# MiataPopUpEnhancer.net
KiCad netlist of a schematic drawn in EAGLE
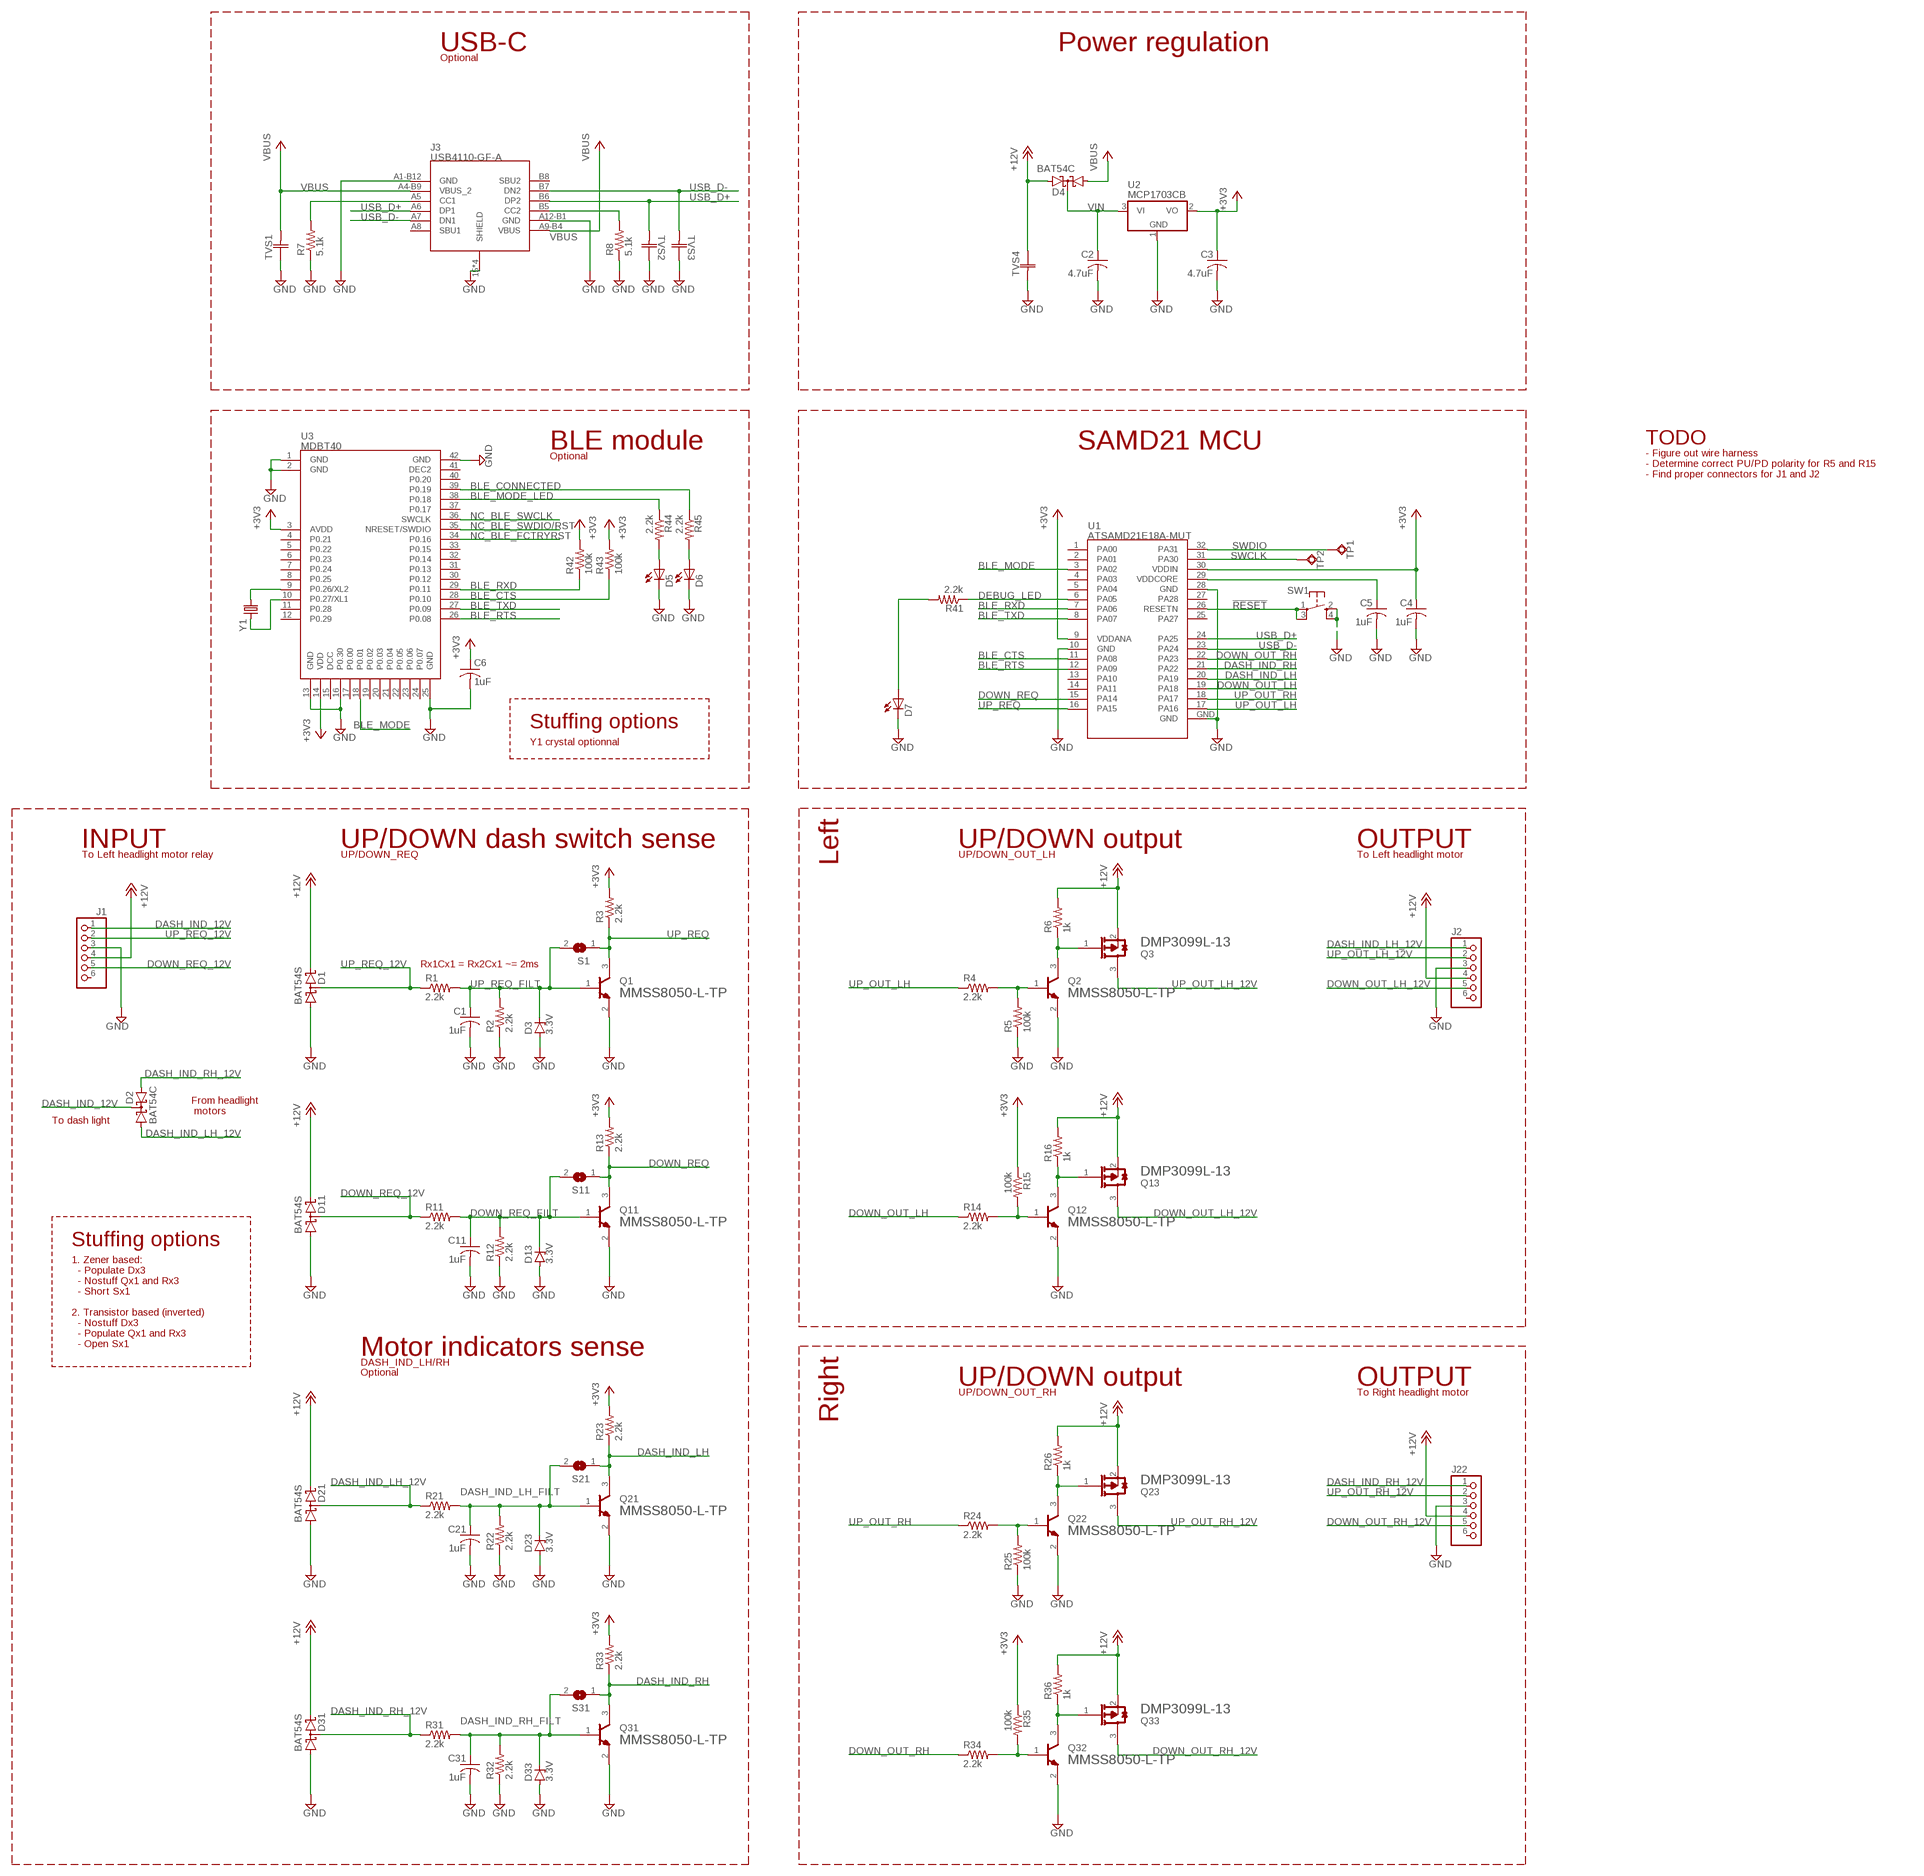
[diagram p0: schematic, sheet 1]

(export (version "E")
  (design (tool "Eeschema 10.0.6"))
  (components
    (comp (ref "C1")
      (value "1uF")
      (footprint "eagle-import:C0603")
      (libsource (lib "eagle-import") (part "C-USC0603"))
    )
    (comp (ref "C2")
      (value "4.7uF")
      (footprint "eagle-import:C0603K")
      (libsource (lib "eagle-import") (part "C-USC0603K"))
    )
    (comp (ref "C3")
      (value "4.7uF")
      (footprint "eagle-import:C0603")
      (libsource (lib "eagle-import") (part "C-USC0603"))
    )
    (comp (ref "C4")
      (value "1uF")
      (footprint "eagle-import:C0603")
      (libsource (lib "eagle-import") (part "C-USC0603"))
    )
    (comp (ref "C5")
      (value "1uF")
      (footprint "eagle-import:C0603")
      (libsource (lib "eagle-import") (part "C-USC0603"))
    )
    (comp (ref "C6")
      (value "1uF")
      (footprint "eagle-import:C0603")
      (libsource (lib "eagle-import") (part "C-USC0603"))
    )
    (comp (ref "C11")
      (value "1uF")
      (footprint "eagle-import:C0603")
      (libsource (lib "eagle-import") (part "C-USC0603"))
    )
    (comp (ref "C21")
      (value "1uF")
      (footprint "eagle-import:C0603")
      (libsource (lib "eagle-import") (part "C-USC0603"))
    )
    (comp (ref "C31")
      (value "1uF")
      (footprint "eagle-import:C0603")
      (libsource (lib "eagle-import") (part "C-USC0603"))
    )
    (comp (ref "D1")
      (value "BAT54S")
      (footprint "eagle-import:SOT23")
      (libsource (lib "eagle-import") (part "BAT54S"))
    )
    (comp (ref "D2")
      (value "BAT54C")
      (footprint "eagle-import:SOT23")
      (libsource (lib "eagle-import") (part "BAT54C"))
    )
    (comp (ref "D3")
      (value "3.3V")
      (footprint "eagle-import:TO236")
      (libsource (lib "eagle-import") (part "BZX84CSMD"))
    )
    (comp (ref "D4")
      (value "BAT54C")
      (footprint "eagle-import:SOT23")
      (libsource (lib "eagle-import") (part "BAT54C"))
    )
    (comp (ref "D5")
      (value "LEDCHIPLED_0603")
      (footprint "eagle-import:CHIPLED_0603")
      (libsource (lib "eagle-import") (part "LEDCHIPLED_0603"))
    )
    (comp (ref "D6")
      (value "LEDCHIPLED_0603")
      (footprint "eagle-import:CHIPLED_0603")
      (libsource (lib "eagle-import") (part "LEDCHIPLED_0603"))
    )
    (comp (ref "D7")
      (value "LEDCHIPLED_0603")
      (footprint "eagle-import:CHIPLED_0603")
      (libsource (lib "eagle-import") (part "LEDCHIPLED_0603"))
    )
    (comp (ref "D11")
      (value "BAT54S")
      (footprint "eagle-import:SOT23")
      (libsource (lib "eagle-import") (part "BAT54S"))
    )
    (comp (ref "D13")
      (value "3.3V")
      (footprint "eagle-import:TO236")
      (libsource (lib "eagle-import") (part "BZX84CSMD"))
    )
    (comp (ref "D21")
      (value "BAT54S")
      (footprint "eagle-import:SOT23")
      (libsource (lib "eagle-import") (part "BAT54S"))
    )
    (comp (ref "D23")
      (value "3.3V")
      (footprint "eagle-import:TO236")
      (libsource (lib "eagle-import") (part "BZX84CSMD"))
    )
    (comp (ref "D31")
      (value "BAT54S")
      (footprint "eagle-import:SOT23")
      (libsource (lib "eagle-import") (part "BAT54S"))
    )
    (comp (ref "D33")
      (value "3.3V")
      (footprint "eagle-import:TO236")
      (libsource (lib "eagle-import") (part "BZX84CSMD"))
    )
    (comp (ref "J1")
      (value "PINHD-1X6LOCK")
      (footprint "eagle-import:1X06-BIGLOCK")
      (libsource (lib "eagle-import") (part "PINHD-1X6LOCK"))
    )
    (comp (ref "J2")
      (value "PINHD-1X6LOCK")
      (footprint "eagle-import:1X06-BIGLOCK")
      (libsource (lib "eagle-import") (part "PINHD-1X6LOCK"))
    )
    (comp (ref "J3")
      (value "USB4110-GF-A")
      (footprint "eagle-import:USB4110-GF-A_GCT")
      (fields (field (name "COPYRIGHT") "Copyright (C) 2021 Ultra Librarian. All rights reserved."))
      (libsource (lib "eagle-import") (part "USB4110-GF-A"))
    )
    (comp (ref "J22")
      (value "PINHD-1X6LOCK")
      (footprint "eagle-import:1X06-BIGLOCK")
      (libsource (lib "eagle-import") (part "PINHD-1X6LOCK"))
    )
    (comp (ref "Q1")
      (value "MICRO_COMMERCIAL_MMSS8050-L-TPMICRO_COMMERCIAL_MMSS8050-L-TP_0_0")
      (footprint "eagle-import:MICRO_COMMERCIAL_MMSS8050-L-TP_0")
      (fields
        (field (name "DIGIKEY_PART_NUMBER") "MMSS8050-L-TPMSCT-ND")
        (field (name "MF") "Micro Commercial")
        (field (name "MOUSER_PART_NUMBER") "833-MMSS8050-L-TP")
      )
      (libsource (lib "eagle-import") (part "MICRO_COMMERCIAL_MMSS8050-L-TPMICRO_COMMERCIAL_MMSS8050-L-TP_0_0"))
    )
    (comp (ref "Q2")
      (value "MICRO_COMMERCIAL_MMSS8050-L-TPMICRO_COMMERCIAL_MMSS8050-L-TP_0_0")
      (footprint "eagle-import:MICRO_COMMERCIAL_MMSS8050-L-TP_0")
      (fields
        (field (name "DIGIKEY_PART_NUMBER") "MMSS8050-L-TPMSCT-ND")
        (field (name "MF") "Micro Commercial")
        (field (name "MOUSER_PART_NUMBER") "833-MMSS8050-L-TP")
      )
      (libsource (lib "eagle-import") (part "MICRO_COMMERCIAL_MMSS8050-L-TPMICRO_COMMERCIAL_MMSS8050-L-TP_0_0"))
    )
    (comp (ref "Q3")
      (value "DIODES_INC_DMP3099L-13DIODES_INC_DMP3099L-13_0_0")
      (footprint "eagle-import:DIODES_INC_DMP3099L-13_0")
      (fields
        (field (name "DIGIKEY_PART_NUMBER") "DMP3099L-13DICT-ND")
        (field (name "MF") "Diodes Inc.")
        (field (name "MOUSER_PART_NUMBER") "621-DMP3099L-13")
      )
      (libsource (lib "eagle-import") (part "DIODES_INC_DMP3099L-13DIODES_INC_DMP3099L-13_0_0"))
    )
    (comp (ref "Q11")
      (value "MICRO_COMMERCIAL_MMSS8050-L-TPMICRO_COMMERCIAL_MMSS8050-L-TP_0_0")
      (footprint "eagle-import:MICRO_COMMERCIAL_MMSS8050-L-TP_0")
      (fields
        (field (name "DIGIKEY_PART_NUMBER") "MMSS8050-L-TPMSCT-ND")
        (field (name "MF") "Micro Commercial")
        (field (name "MOUSER_PART_NUMBER") "833-MMSS8050-L-TP")
      )
      (libsource (lib "eagle-import") (part "MICRO_COMMERCIAL_MMSS8050-L-TPMICRO_COMMERCIAL_MMSS8050-L-TP_0_0"))
    )
    (comp (ref "Q12")
      (value "MICRO_COMMERCIAL_MMSS8050-L-TPMICRO_COMMERCIAL_MMSS8050-L-TP_0_0")
      (footprint "eagle-import:MICRO_COMMERCIAL_MMSS8050-L-TP_0")
      (fields
        (field (name "DIGIKEY_PART_NUMBER") "MMSS8050-L-TPMSCT-ND")
        (field (name "MF") "Micro Commercial")
        (field (name "MOUSER_PART_NUMBER") "833-MMSS8050-L-TP")
      )
      (libsource (lib "eagle-import") (part "MICRO_COMMERCIAL_MMSS8050-L-TPMICRO_COMMERCIAL_MMSS8050-L-TP_0_0"))
    )
    (comp (ref "Q13")
      (value "DIODES_INC_DMP3099L-13DIODES_INC_DMP3099L-13_0_0")
      (footprint "eagle-import:DIODES_INC_DMP3099L-13_0")
      (fields
        (field (name "DIGIKEY_PART_NUMBER") "DMP3099L-13DICT-ND")
        (field (name "MF") "Diodes Inc.")
        (field (name "MOUSER_PART_NUMBER") "621-DMP3099L-13")
      )
      (libsource (lib "eagle-import") (part "DIODES_INC_DMP3099L-13DIODES_INC_DMP3099L-13_0_0"))
    )
    (comp (ref "Q21")
      (value "MICRO_COMMERCIAL_MMSS8050-L-TPMICRO_COMMERCIAL_MMSS8050-L-TP_0_0")
      (footprint "eagle-import:MICRO_COMMERCIAL_MMSS8050-L-TP_0")
      (fields
        (field (name "DIGIKEY_PART_NUMBER") "MMSS8050-L-TPMSCT-ND")
        (field (name "MF") "Micro Commercial")
        (field (name "MOUSER_PART_NUMBER") "833-MMSS8050-L-TP")
      )
      (libsource (lib "eagle-import") (part "MICRO_COMMERCIAL_MMSS8050-L-TPMICRO_COMMERCIAL_MMSS8050-L-TP_0_0"))
    )
    (comp (ref "Q22")
      (value "MICRO_COMMERCIAL_MMSS8050-L-TPMICRO_COMMERCIAL_MMSS8050-L-TP_0_0")
      (footprint "eagle-import:MICRO_COMMERCIAL_MMSS8050-L-TP_0")
      (fields
        (field (name "DIGIKEY_PART_NUMBER") "MMSS8050-L-TPMSCT-ND")
        (field (name "MF") "Micro Commercial")
        (field (name "MOUSER_PART_NUMBER") "833-MMSS8050-L-TP")
      )
      (libsource (lib "eagle-import") (part "MICRO_COMMERCIAL_MMSS8050-L-TPMICRO_COMMERCIAL_MMSS8050-L-TP_0_0"))
    )
    (comp (ref "Q23")
      (value "DIODES_INC_DMP3099L-13DIODES_INC_DMP3099L-13_0_0")
      (footprint "eagle-import:DIODES_INC_DMP3099L-13_0")
      (fields
        (field (name "DIGIKEY_PART_NUMBER") "DMP3099L-13DICT-ND")
        (field (name "MF") "Diodes Inc.")
        (field (name "MOUSER_PART_NUMBER") "621-DMP3099L-13")
      )
      (libsource (lib "eagle-import") (part "DIODES_INC_DMP3099L-13DIODES_INC_DMP3099L-13_0_0"))
    )
    (comp (ref "Q31")
      (value "MICRO_COMMERCIAL_MMSS8050-L-TPMICRO_COMMERCIAL_MMSS8050-L-TP_0_0")
      (footprint "eagle-import:MICRO_COMMERCIAL_MMSS8050-L-TP_0")
      (fields
        (field (name "DIGIKEY_PART_NUMBER") "MMSS8050-L-TPMSCT-ND")
        (field (name "MF") "Micro Commercial")
        (field (name "MOUSER_PART_NUMBER") "833-MMSS8050-L-TP")
      )
      (libsource (lib "eagle-import") (part "MICRO_COMMERCIAL_MMSS8050-L-TPMICRO_COMMERCIAL_MMSS8050-L-TP_0_0"))
    )
    (comp (ref "Q32")
      (value "MICRO_COMMERCIAL_MMSS8050-L-TPMICRO_COMMERCIAL_MMSS8050-L-TP_0_0")
      (footprint "eagle-import:MICRO_COMMERCIAL_MMSS8050-L-TP_0")
      (fields
        (field (name "DIGIKEY_PART_NUMBER") "MMSS8050-L-TPMSCT-ND")
        (field (name "MF") "Micro Commercial")
        (field (name "MOUSER_PART_NUMBER") "833-MMSS8050-L-TP")
      )
      (libsource (lib "eagle-import") (part "MICRO_COMMERCIAL_MMSS8050-L-TPMICRO_COMMERCIAL_MMSS8050-L-TP_0_0"))
    )
    (comp (ref "Q33")
      (value "DIODES_INC_DMP3099L-13DIODES_INC_DMP3099L-13_0_0")
      (footprint "eagle-import:DIODES_INC_DMP3099L-13_0")
      (fields
        (field (name "DIGIKEY_PART_NUMBER") "DMP3099L-13DICT-ND")
        (field (name "MF") "Diodes Inc.")
        (field (name "MOUSER_PART_NUMBER") "621-DMP3099L-13")
      )
      (libsource (lib "eagle-import") (part "DIODES_INC_DMP3099L-13DIODES_INC_DMP3099L-13_0_0"))
    )
    (comp (ref "R1")
      (value "2.2k")
      (footprint "eagle-import:R0603")
      (libsource (lib "eagle-import") (part "R-US_R0603"))
    )
    (comp (ref "R2")
      (value "2.2k")
      (footprint "eagle-import:R0603")
      (libsource (lib "eagle-import") (part "R-US_R0603"))
    )
    (comp (ref "R3")
      (value "2.2k")
      (footprint "eagle-import:R0603")
      (libsource (lib "eagle-import") (part "R-US_R0603"))
    )
    (comp (ref "R4")
      (value "2.2k")
      (footprint "eagle-import:R0603")
      (libsource (lib "eagle-import") (part "R-US_R0603"))
    )
    (comp (ref "R5")
      (value "100k")
      (footprint "eagle-import:R0603")
      (libsource (lib "eagle-import") (part "R-US_R0603"))
    )
    (comp (ref "R6")
      (value "1k")
      (footprint "eagle-import:R0603")
      (libsource (lib "eagle-import") (part "R-US_R0603"))
    )
    (comp (ref "R7")
      (value "5.1k")
      (footprint "eagle-import:R0603")
      (libsource (lib "eagle-import") (part "R-US_R0603"))
    )
    (comp (ref "R8")
      (value "5.1k")
      (footprint "eagle-import:R0603")
      (libsource (lib "eagle-import") (part "R-US_R0603"))
    )
    (comp (ref "R11")
      (value "2.2k")
      (footprint "eagle-import:R0603")
      (libsource (lib "eagle-import") (part "R-US_R0603"))
    )
    (comp (ref "R12")
      (value "2.2k")
      (footprint "eagle-import:R0603")
      (libsource (lib "eagle-import") (part "R-US_R0603"))
    )
    (comp (ref "R13")
      (value "2.2k")
      (footprint "eagle-import:R0603")
      (libsource (lib "eagle-import") (part "R-US_R0603"))
    )
    (comp (ref "R14")
      (value "2.2k")
      (footprint "eagle-import:R0603")
      (libsource (lib "eagle-import") (part "R-US_R0603"))
    )
    (comp (ref "R15")
      (value "100k")
      (footprint "eagle-import:R0603")
      (libsource (lib "eagle-import") (part "R-US_R0603"))
    )
    (comp (ref "R16")
      (value "1k")
      (footprint "eagle-import:R0603")
      (libsource (lib "eagle-import") (part "R-US_R0603"))
    )
    (comp (ref "R21")
      (value "2.2k")
      (footprint "eagle-import:R0603")
      (libsource (lib "eagle-import") (part "R-US_R0603"))
    )
    (comp (ref "R22")
      (value "2.2k")
      (footprint "eagle-import:R0603")
      (libsource (lib "eagle-import") (part "R-US_R0603"))
    )
    (comp (ref "R23")
      (value "2.2k")
      (footprint "eagle-import:R0603")
      (libsource (lib "eagle-import") (part "R-US_R0603"))
    )
    (comp (ref "R24")
      (value "2.2k")
      (footprint "eagle-import:R0603")
      (libsource (lib "eagle-import") (part "R-US_R0603"))
    )
    (comp (ref "R25")
      (value "100k")
      (footprint "eagle-import:R0603")
      (libsource (lib "eagle-import") (part "R-US_R0603"))
    )
    (comp (ref "R26")
      (value "1k")
      (footprint "eagle-import:R0603")
      (libsource (lib "eagle-import") (part "R-US_R0603"))
    )
    (comp (ref "R31")
      (value "2.2k")
      (footprint "eagle-import:R0603")
      (libsource (lib "eagle-import") (part "R-US_R0603"))
    )
    (comp (ref "R32")
      (value "2.2k")
      (footprint "eagle-import:R0603")
      (libsource (lib "eagle-import") (part "R-US_R0603"))
    )
    (comp (ref "R33")
      (value "2.2k")
      (footprint "eagle-import:R0603")
      (libsource (lib "eagle-import") (part "R-US_R0603"))
    )
    (comp (ref "R34")
      (value "2.2k")
      (footprint "eagle-import:R0603")
      (libsource (lib "eagle-import") (part "R-US_R0603"))
    )
    (comp (ref "R35")
      (value "100k")
      (footprint "eagle-import:R0603")
      (libsource (lib "eagle-import") (part "R-US_R0603"))
    )
    (comp (ref "R36")
      (value "1k")
      (footprint "eagle-import:R0603")
      (libsource (lib "eagle-import") (part "R-US_R0603"))
    )
    (comp (ref "R41")
      (value "2.2k")
      (footprint "eagle-import:R0603")
      (libsource (lib "eagle-import") (part "R-US_R0603"))
    )
    (comp (ref "R42")
      (value "100k")
      (footprint "eagle-import:R0603")
      (libsource (lib "eagle-import") (part "R-US_R0603"))
    )
    (comp (ref "R43")
      (value "100k")
      (footprint "eagle-import:R0603")
      (libsource (lib "eagle-import") (part "R-US_R0603"))
    )
    (comp (ref "R44")
      (value "2.2k")
      (footprint "eagle-import:R0603")
      (libsource (lib "eagle-import") (part "R-US_R0603"))
    )
    (comp (ref "R45")
      (value "2.2k")
      (footprint "eagle-import:R0603")
      (libsource (lib "eagle-import") (part "R-US_R0603"))
    )
    (comp (ref "S1") (value "SJ") (footprint "eagle-import:SJ") (libsource (lib "eagle-import") (part "SJ")))
    (comp (ref "S11") (value "SJ") (footprint "eagle-import:SJ") (libsource (lib "eagle-import") (part "SJ")))
    (comp (ref "S21") (value "SJ") (footprint "eagle-import:SJ") (libsource (lib "eagle-import") (part "SJ")))
    (comp (ref "S31") (value "SJ") (footprint "eagle-import:SJ") (libsource (lib "eagle-import") (part "SJ")))
    (comp (ref "SW1")
      (value "KMR2")
      (footprint "eagle-import:KMR2")
      (libsource (lib "eagle-import") (part "SPST_TACT-KMR2"))
    )
    (comp (ref "TP1")
      (value "TPSQB2,54")
      (footprint "eagle-import:B2,54")
      (libsource (lib "eagle-import") (part "TPSQB2,54"))
    )
    (comp (ref "TP2")
      (value "TPSQB2,54")
      (footprint "eagle-import:B2,54")
      (libsource (lib "eagle-import") (part "TPSQB2,54"))
    )
    (comp (ref "TVS1")
      (value "ESDU02A5V5R17V")
      (footprint "eagle-import:CAP_ESDU02_STP")
      (fields (field (name "COPYRIGHT") "Copyright (C) 2021 Ultra Librarian. All rights reserved."))
      (libsource (lib "eagle-import") (part "ESDU02A5V5R17V"))
    )
    (comp (ref "TVS2")
      (value "ESDU02A5V5R17V")
      (footprint "eagle-import:CAP_ESDU02_STP")
      (fields (field (name "COPYRIGHT") "Copyright (C) 2021 Ultra Librarian. All rights reserved."))
      (libsource (lib "eagle-import") (part "ESDU02A5V5R17V"))
    )
    (comp (ref "TVS3")
      (value "ESDU02A5V5R17V")
      (footprint "eagle-import:CAP_ESDU02_STP")
      (fields (field (name "COPYRIGHT") "Copyright (C) 2021 Ultra Librarian. All rights reserved."))
      (libsource (lib "eagle-import") (part "ESDU02A5V5R17V"))
    )
    (comp (ref "TVS4")
      (value "ESDU02A5V5R17V")
      (footprint "eagle-import:CAP_ESDU02_STP")
      (fields (field (name "COPYRIGHT") "Copyright (C) 2021 Ultra Librarian. All rights reserved."))
      (libsource (lib "eagle-import") (part "ESDU02A5V5R17V"))
    )
    (comp (ref "U1")
      (value "ATSAMD21E18A-MUT")
      (footprint "eagle-import:QFN32")
      (libsource (lib "eagle-import") (part "ATSAMD21E18A-MUT"))
    )
    (comp (ref "U2")
      (value "MCP1703CB")
      (footprint "eagle-import:SOT23")
      (libsource (lib "eagle-import") (part "MCP1703CB"))
    )
    (comp (ref "U3")
      (value "MDBT40")
      (footprint "eagle-import:MDBT40")
      (libsource (lib "eagle-import") (part "MDBT40"))
    )
    (comp (ref "Y1")
      (value "ABS25-32.768KHZ-T")
      (footprint "eagle-import:MM20SS")
      (libsource (lib "eagle-import") (part "CRYSTALMM20SS"))
    )
  )
  (nets
    (net (code "1") (name "+3V3") (class "Default")
      (node (ref "C3") (pin "1") (pinfunction "1_1") (pintype "passive"))
      (node (ref "C4") (pin "1") (pinfunction "1_1") (pintype "passive"))
      (node (ref "C6") (pin "1") (pinfunction "1_1") (pintype "passive"))
      (node (ref "R13") (pin "2") (pinfunction "2_2") (pintype "passive"))
      (node (ref "R15") (pin "1") (pinfunction "1_1") (pintype "passive"))
      (node (ref "R23") (pin "2") (pinfunction "2_2") (pintype "passive"))
      (node (ref "R3") (pin "2") (pinfunction "2_2") (pintype "passive"))
      (node (ref "R33") (pin "2") (pinfunction "2_2") (pintype "passive"))
      (node (ref "R35") (pin "1") (pinfunction "1_1") (pintype "passive"))
      (node (ref "R42") (pin "2") (pinfunction "2_2") (pintype "passive"))
      (node (ref "R43") (pin "2") (pinfunction "2_2") (pintype "passive"))
      (node (ref "U1") (pin "30") (pinfunction "VDDIN_30") (pintype "bidirectional"))
      (node (ref "U1") (pin "9") (pinfunction "VDDANA_9") (pintype "bidirectional"))
      (node (ref "U2") (pin "2") (pinfunction "VO_2") (pintype "passive"))
      (node (ref "U3") (pin "14") (pinfunction "VDD_14") (pintype "bidirectional"))
      (node (ref "U3") (pin "3") (pinfunction "AVDD_3") (pintype "bidirectional"))
    )
    (net (code "2") (name "+12V") (class "Default")
      (node (ref "D1") (pin "2") (pinfunction "C2_2") (pintype "passive"))
      (node (ref "D11") (pin "2") (pinfunction "C2_2") (pintype "passive"))
      (node (ref "D21") (pin "2") (pinfunction "C2_2") (pintype "passive"))
      (node (ref "D31") (pin "2") (pinfunction "C2_2") (pintype "passive"))
      (node (ref "D4") (pin "2") (pinfunction "A2_2") (pintype "passive"))
      (node (ref "J1") (pin "4") (pinfunction "4_4") (pintype "passive"))
      (node (ref "J2") (pin "4") (pinfunction "4_4") (pintype "passive"))
      (node (ref "J22") (pin "4") (pinfunction "4_4") (pintype "passive"))
      (node (ref "Q13") (pin "2") (pinfunction "S_2") (pintype "passive"))
      (node (ref "Q23") (pin "2") (pinfunction "S_2") (pintype "passive"))
      (node (ref "Q3") (pin "2") (pinfunction "S_2") (pintype "passive"))
      (node (ref "Q33") (pin "2") (pinfunction "S_2") (pintype "passive"))
      (node (ref "R16") (pin "2") (pinfunction "2_2") (pintype "passive"))
      (node (ref "R26") (pin "2") (pinfunction "2_2") (pintype "passive"))
      (node (ref "R36") (pin "2") (pinfunction "2_2") (pintype "passive"))
      (node (ref "R6") (pin "2") (pinfunction "2_2") (pintype "passive"))
      (node (ref "TVS4") (pin "1") (pinfunction "1_1") (pintype "passive"))
    )
    (net (code "3") (name "/BLE_CONNECTED") (class "Default")
      (node (ref "R45") (pin "1") (pinfunction "1_1") (pintype "passive"))
      (node (ref "U3") (pin "39") (pinfunction "P0.19_39") (pintype "bidirectional"))
    )
    (net (code "4") (name "/BLE_CTS") (class "Default")
      (node (ref "R43") (pin "1") (pinfunction "1_1") (pintype "passive"))
      (node (ref "U1") (pin "11") (pinfunction "PA08_11") (pintype "bidirectional"))
      (node (ref "U3") (pin "28") (pinfunction "P0.10_28") (pintype "bidirectional"))
    )
    (net (code "5") (name "/BLE_MODE") (class "Default")
      (node (ref "U1") (pin "3") (pinfunction "PA02_3") (pintype "bidirectional"))
      (node (ref "U3") (pin "18") (pinfunction "P0.01_18") (pintype "bidirectional"))
    )
    (net (code "6") (name "/BLE_MODE_LED") (class "Default")
      (node (ref "R44") (pin "1") (pinfunction "1_1") (pintype "passive"))
      (node (ref "U3") (pin "38") (pinfunction "P0.18_38") (pintype "bidirectional"))
    )
    (net (code "7") (name "/BLE_RTS") (class "Default")
      (node (ref "U1") (pin "12") (pinfunction "PA09_12") (pintype "bidirectional"))
      (node (ref "U3") (pin "26") (pinfunction "P0.08_26") (pintype "bidirectional"))
    )
    (net (code "8") (name "/BLE_RXD") (class "Default")
      (node (ref "R42") (pin "1") (pinfunction "1_1") (pintype "passive"))
      (node (ref "U1") (pin "7") (pinfunction "PA06_7") (pintype "bidirectional"))
      (node (ref "U3") (pin "29") (pinfunction "P0.11_29") (pintype "bidirectional"))
    )
    (net (code "9") (name "/BLE_TXD") (class "Default")
      (node (ref "U1") (pin "8") (pinfunction "PA07_8") (pintype "bidirectional"))
      (node (ref "U3") (pin "27") (pinfunction "P0.09_27") (pintype "bidirectional"))
    )
    (net (code "10") (name "/DASH_IND_12V") (class "Default")
      (node (ref "D2") (pin "3") (pinfunction "CC_3") (pintype "passive"))
      (node (ref "J1") (pin "1") (pinfunction "1_1") (pintype "passive"))
    )
    (net (code "11") (name "/DASH_IND_LH") (class "Default")
      (node (ref "Q21") (pin "3") (pinfunction "C_3") (pintype "bidirectional"))
      (node (ref "R23") (pin "1") (pinfunction "1_1") (pintype "passive"))
      (node (ref "S21") (pin "1") (pinfunction "1_1") (pintype "passive"))
      (node (ref "U1") (pin "20") (pinfunction "PA19_20") (pintype "bidirectional"))
    )
    (net (code "12") (name "/DASH_IND_LH_12V") (class "Default")
      (node (ref "D2") (pin "1") (pinfunction "A1_1") (pintype "passive"))
      (node (ref "D21") (pin "3") (pinfunction "C1A2_3") (pintype "passive"))
      (node (ref "J2") (pin "1") (pinfunction "1_1") (pintype "passive"))
      (node (ref "R21") (pin "1") (pinfunction "1_1") (pintype "passive"))
    )
    (net (code "13") (name "/DASH_IND_LH_FILT") (class "Default")
      (node (ref "C21") (pin "1") (pinfunction "1_1") (pintype "passive"))
      (node (ref "D23") (pin "C") (pinfunction "C_C") (pintype "passive"))
      (node (ref "Q21") (pin "1") (pinfunction "B_1") (pintype "bidirectional"))
      (node (ref "R21") (pin "2") (pinfunction "2_2") (pintype "passive"))
      (node (ref "R22") (pin "2") (pinfunction "2_2") (pintype "passive"))
      (node (ref "S21") (pin "2") (pinfunction "2_2") (pintype "passive"))
    )
    (net (code "14") (name "/DASH_IND_RH") (class "Default")
      (node (ref "Q31") (pin "3") (pinfunction "C_3") (pintype "bidirectional"))
      (node (ref "R33") (pin "1") (pinfunction "1_1") (pintype "passive"))
      (node (ref "S31") (pin "1") (pinfunction "1_1") (pintype "passive"))
      (node (ref "U1") (pin "21") (pinfunction "PA22_21") (pintype "bidirectional"))
    )
    (net (code "15") (name "/DASH_IND_RH_12V") (class "Default")
      (node (ref "D2") (pin "2") (pinfunction "A2_2") (pintype "passive"))
      (node (ref "D31") (pin "3") (pinfunction "C1A2_3") (pintype "passive"))
      (node (ref "J22") (pin "1") (pinfunction "1_1") (pintype "passive"))
      (node (ref "R31") (pin "1") (pinfunction "1_1") (pintype "passive"))
    )
    (net (code "16") (name "/DASH_IND_RH_FILT") (class "Default")
      (node (ref "C31") (pin "1") (pinfunction "1_1") (pintype "passive"))
      (node (ref "D33") (pin "C") (pinfunction "C_C") (pintype "passive"))
      (node (ref "Q31") (pin "1") (pinfunction "B_1") (pintype "bidirectional"))
      (node (ref "R31") (pin "2") (pinfunction "2_2") (pintype "passive"))
      (node (ref "R32") (pin "2") (pinfunction "2_2") (pintype "passive"))
      (node (ref "S31") (pin "2") (pinfunction "2_2") (pintype "passive"))
    )
    (net (code "17") (name "/DEBUG_LED") (class "Default")
      (node (ref "R41") (pin "1") (pinfunction "1_1") (pintype "passive"))
      (node (ref "U1") (pin "6") (pinfunction "PA05_6") (pintype "bidirectional"))
    )
    (net (code "18") (name "/DOWN_OUT_LH") (class "Default")
      (node (ref "R14") (pin "1") (pinfunction "1_1") (pintype "passive"))
      (node (ref "U1") (pin "19") (pinfunction "PA18_19") (pintype "bidirectional"))
    )
    (net (code "19") (name "/DOWN_OUT_LH_12V") (class "Default")
      (node (ref "J2") (pin "5") (pinfunction "5_5") (pintype "passive"))
      (node (ref "Q13") (pin "3") (pinfunction "D_3") (pintype "passive"))
    )
    (net (code "20") (name "/DOWN_OUT_RH") (class "Default")
      (node (ref "R34") (pin "1") (pinfunction "1_1") (pintype "passive"))
      (node (ref "U1") (pin "22") (pinfunction "PA23_22") (pintype "bidirectional"))
    )
    (net (code "21") (name "/DOWN_OUT_RH_12V") (class "Default")
      (node (ref "J22") (pin "5") (pinfunction "5_5") (pintype "passive"))
      (node (ref "Q33") (pin "3") (pinfunction "D_3") (pintype "passive"))
    )
    (net (code "22") (name "/DOWN_REQ") (class "Default")
      (node (ref "Q11") (pin "3") (pinfunction "C_3") (pintype "bidirectional"))
      (node (ref "R13") (pin "1") (pinfunction "1_1") (pintype "passive"))
      (node (ref "S11") (pin "1") (pinfunction "1_1") (pintype "passive"))
      (node (ref "U1") (pin "15") (pinfunction "PA14_15") (pintype "bidirectional"))
    )
    (net (code "23") (name "/DOWN_REQ_12V") (class "Default")
      (node (ref "D11") (pin "3") (pinfunction "C1A2_3") (pintype "passive"))
      (node (ref "J1") (pin "5") (pinfunction "5_5") (pintype "passive"))
      (node (ref "R11") (pin "1") (pinfunction "1_1") (pintype "passive"))
    )
    (net (code "24") (name "/DOWN_REQ_FILT") (class "Default")
      (node (ref "C11") (pin "1") (pinfunction "1_1") (pintype "passive"))
      (node (ref "D13") (pin "C") (pinfunction "C_C") (pintype "passive"))
      (node (ref "Q11") (pin "1") (pinfunction "B_1") (pintype "bidirectional"))
      (node (ref "R11") (pin "2") (pinfunction "2_2") (pintype "passive"))
      (node (ref "R12") (pin "2") (pinfunction "2_2") (pintype "passive"))
      (node (ref "S11") (pin "2") (pinfunction "2_2") (pintype "passive"))
    )
    (net (code "25") (name "/NC_BLE_FCTRYRST") (class "Default")
      (node (ref "U3") (pin "34") (pinfunction "P0.16_34") (pintype "bidirectional"))
    )
    (net (code "26") (name "/NC_BLE_SWCLK") (class "Default")
      (node (ref "U3") (pin "36") (pinfunction "SWCLK_36") (pintype "bidirectional"))
    )
    (net (code "27") (name "/NC_BLE_SWDIO{slash}RST") (class "Default")
      (node (ref "U3") (pin "35") (pinfunction "NRESET/SWDIO_35") (pintype "bidirectional"))
    )
    (net (code "28") (name "/SWCLK") (class "Default")
      (node (ref "TP2") (pin "TP") (pinfunction "TP_TP") (pintype "input"))
      (node (ref "U1") (pin "31") (pinfunction "PA30_31") (pintype "bidirectional"))
    )
    (net (code "29") (name "/SWDIO") (class "Default")
      (node (ref "TP1") (pin "TP") (pinfunction "TP_TP") (pintype "input"))
      (node (ref "U1") (pin "32") (pinfunction "PA31_32") (pintype "bidirectional"))
    )
    (net (code "30") (name "/UP_OUT_LH") (class "Default")
      (node (ref "R4") (pin "1") (pinfunction "1_1") (pintype "passive"))
      (node (ref "U1") (pin "17") (pinfunction "PA16_17") (pintype "bidirectional"))
    )
    (net (code "31") (name "/UP_OUT_LH_12V") (class "Default")
      (node (ref "J2") (pin "2") (pinfunction "2_2") (pintype "passive"))
      (node (ref "Q3") (pin "3") (pinfunction "D_3") (pintype "passive"))
    )
    (net (code "32") (name "/UP_OUT_RH") (class "Default")
      (node (ref "R24") (pin "1") (pinfunction "1_1") (pintype "passive"))
      (node (ref "U1") (pin "18") (pinfunction "PA17_18") (pintype "bidirectional"))
    )
    (net (code "33") (name "/UP_OUT_RH_12V") (class "Default")
      (node (ref "J22") (pin "2") (pinfunction "2_2") (pintype "passive"))
      (node (ref "Q23") (pin "3") (pinfunction "D_3") (pintype "passive"))
    )
    (net (code "34") (name "/UP_REQ") (class "Default")
      (node (ref "Q1") (pin "3") (pinfunction "C_3") (pintype "bidirectional"))
      (node (ref "R3") (pin "1") (pinfunction "1_1") (pintype "passive"))
      (node (ref "S1") (pin "1") (pinfunction "1_1") (pintype "passive"))
      (node (ref "U1") (pin "16") (pinfunction "PA15_16") (pintype "bidirectional"))
    )
    (net (code "35") (name "/UP_REQ_12V") (class "Default")
      (node (ref "D1") (pin "3") (pinfunction "C1A2_3") (pintype "passive"))
      (node (ref "J1") (pin "2") (pinfunction "2_2") (pintype "passive"))
      (node (ref "R1") (pin "1") (pinfunction "1_1") (pintype "passive"))
    )
    (net (code "36") (name "/UP_REQ_FILT") (class "Default")
      (node (ref "C1") (pin "1") (pinfunction "1_1") (pintype "passive"))
      (node (ref "D3") (pin "C") (pinfunction "C_C") (pintype "passive"))
      (node (ref "Q1") (pin "1") (pinfunction "B_1") (pintype "bidirectional"))
      (node (ref "R1") (pin "2") (pinfunction "2_2") (pintype "passive"))
      (node (ref "R2") (pin "2") (pinfunction "2_2") (pintype "passive"))
      (node (ref "S1") (pin "2") (pinfunction "2_2") (pintype "passive"))
    )
    (net (code "37") (name "/USB_D+") (class "Default")
      (node (ref "J3") (pin "A6") (pinfunction "DP1_A6") (pintype "bidirectional"))
      (node (ref "J3") (pin "B6") (pinfunction "DP2_B6") (pintype "bidirectional"))
      (node (ref "TVS2") (pin "2") (pinfunction "2_2") (pintype "passive"))
      (node (ref "U1") (pin "24") (pinfunction "PA25_24") (pintype "bidirectional"))
    )
    (net (code "38") (name "/USB_D-") (class "Default")
      (node (ref "J3") (pin "A7") (pinfunction "DN1_A7") (pintype "bidirectional"))
      (node (ref "J3") (pin "B7") (pinfunction "DN2_B7") (pintype "bidirectional"))
      (node (ref "TVS3") (pin "2") (pinfunction "2_2") (pintype "passive"))
      (node (ref "U1") (pin "23") (pinfunction "PA24_23") (pintype "bidirectional"))
    )
    (net (code "39") (name "/VIN") (class "Default")
      (node (ref "C2") (pin "1") (pinfunction "1_1") (pintype "passive"))
      (node (ref "D4") (pin "3") (pinfunction "CC_3") (pintype "passive"))
      (node (ref "U2") (pin "3") (pinfunction "VI_3") (pintype "input"))
    )
    (net (code "40") (name "/~{RESET}") (class "Default")
      (node (ref "SW1") (pin "1") (pinfunction "P_1") (pintype "passive"))
      (node (ref "SW1") (pin "3") (pinfunction "P1_3") (pintype "passive"))
      (node (ref "U1") (pin "26") (pinfunction "RESETN_26") (pintype "bidirectional"))
    )
    (net (code "41") (name "GND") (class "Default")
      (node (ref "C1") (pin "2") (pinfunction "2_2") (pintype "passive"))
      (node (ref "C11") (pin "2") (pinfunction "2_2") (pintype "passive"))
      (node (ref "C2") (pin "2") (pinfunction "2_2") (pintype "passive"))
      (node (ref "C21") (pin "2") (pinfunction "2_2") (pintype "passive"))
      (node (ref "C3") (pin "2") (pinfunction "2_2") (pintype "passive"))
      (node (ref "C31") (pin "2") (pinfunction "2_2") (pintype "passive"))
      (node (ref "C4") (pin "2") (pinfunction "2_2") (pintype "passive"))
      (node (ref "C5") (pin "2") (pinfunction "2_2") (pintype "passive"))
      (node (ref "C6") (pin "2") (pinfunction "2_2") (pintype "passive"))
      (node (ref "D1") (pin "1") (pinfunction "A1_1") (pintype "passive"))
      (node (ref "D11") (pin "1") (pinfunction "A1_1") (pintype "passive"))
      (node (ref "D13") (pin "A") (pinfunction "A_A") (pintype "passive"))
      (node (ref "D21") (pin "1") (pinfunction "A1_1") (pintype "passive"))
      (node (ref "D23") (pin "A") (pinfunction "A_A") (pintype "passive"))
      (node (ref "D3") (pin "A") (pinfunction "A_A") (pintype "passive"))
      (node (ref "D31") (pin "1") (pinfunction "A1_1") (pintype "passive"))
      (node (ref "D33") (pin "A") (pinfunction "A_A") (pintype "passive"))
      (node (ref "D5") (pin "C") (pinfunction "C_C") (pintype "passive"))
      (node (ref "D6") (pin "C") (pinfunction "C_C") (pintype "passive"))
      (node (ref "D7") (pin "C") (pinfunction "C_C") (pintype "passive"))
      (node (ref "J1") (pin "3") (pinfunction "3_3") (pintype "passive"))
      (node (ref "J2") (pin "3") (pinfunction "3_3") (pintype "passive"))
      (node (ref "J22") (pin "3") (pinfunction "3_3") (pintype "passive"))
      (node (ref "J3") (pin "15") (pinfunction "SHIELD_15") (pintype "passive"))
      (node (ref "J3") (pin "16") (pinfunction "SHIELD_16") (pintype "passive"))
      (node (ref "J3") (pin "17") (pinfunction "SHIELD_17") (pintype "passive"))
      (node (ref "J3") (pin "18") (pinfunction "SHIELD_18") (pintype "passive"))
      (node (ref "J3") (pin "A1-B12") (pinfunction "GND_A1-B12") (pintype "passive"))
      (node (ref "J3") (pin "A12-B1") (pinfunction "GND_A12-B1") (pintype "passive"))
      (node (ref "Q1") (pin "2") (pinfunction "E_2") (pintype "bidirectional"))
      (node (ref "Q11") (pin "2") (pinfunction "E_2") (pintype "bidirectional"))
      (node (ref "Q12") (pin "2") (pinfunction "E_2") (pintype "bidirectional"))
      (node (ref "Q2") (pin "2") (pinfunction "E_2") (pintype "bidirectional"))
      (node (ref "Q21") (pin "2") (pinfunction "E_2") (pintype "bidirectional"))
      (node (ref "Q22") (pin "2") (pinfunction "E_2") (pintype "bidirectional"))
      (node (ref "Q31") (pin "2") (pinfunction "E_2") (pintype "bidirectional"))
      (node (ref "Q32") (pin "2") (pinfunction "E_2") (pintype "bidirectional"))
      (node (ref "R12") (pin "1") (pinfunction "1_1") (pintype "passive"))
      (node (ref "R2") (pin "1") (pinfunction "1_1") (pintype "passive"))
      (node (ref "R22") (pin "1") (pinfunction "1_1") (pintype "passive"))
      (node (ref "R25") (pin "1") (pinfunction "1_1") (pintype "passive"))
      (node (ref "R32") (pin "1") (pinfunction "1_1") (pintype "passive"))
      (node (ref "R5") (pin "1") (pinfunction "1_1") (pintype "passive"))
      (node (ref "R7") (pin "1") (pinfunction "1_1") (pintype "passive"))
      (node (ref "R8") (pin "1") (pinfunction "1_1") (pintype "passive"))
      (node (ref "SW1") (pin "2") (pinfunction "S_2") (pintype "passive"))
      (node (ref "SW1") (pin "4") (pinfunction "S1_4") (pintype "passive"))
      (node (ref "TVS1") (pin "1") (pinfunction "1_1") (pintype "passive"))
      (node (ref "TVS2") (pin "1") (pinfunction "1_1") (pintype "passive"))
      (node (ref "TVS3") (pin "1") (pinfunction "1_1") (pintype "passive"))
      (node (ref "TVS4") (pin "2") (pinfunction "2_2") (pintype "passive"))
      (node (ref "U1") (pin "10") (pinfunction "GND_10") (pintype "bidirectional"))
      (node (ref "U1") (pin "28") (pinfunction "GND_28") (pintype "bidirectional"))
      (node (ref "U1") (pin "GND") (pinfunction "GND_GND") (pintype "bidirectional"))
      (node (ref "U2") (pin "1") (pinfunction "GND_1") (pintype "passive"))
      (node (ref "U3") (pin "1") (pinfunction "GND_1") (pintype "bidirectional"))
      (node (ref "U3") (pin "13") (pinfunction "GND_13") (pintype "bidirectional"))
      (node (ref "U3") (pin "16") (pinfunction "P0.30_16") (pintype "bidirectional"))
      (node (ref "U3") (pin "2") (pinfunction "GND_2") (pintype "bidirectional"))
      (node (ref "U3") (pin "25") (pinfunction "GND_25") (pintype "bidirectional"))
      (node (ref "U3") (pin "42") (pinfunction "GND_42") (pintype "bidirectional"))
    )
    (net (code "42") (name "Net-(D5-PadA)") (class "Default")
      (node (ref "D5") (pin "A") (pinfunction "A_A") (pintype "passive"))
      (node (ref "R44") (pin "2") (pinfunction "2_2") (pintype "passive"))
    )
    (net (code "43") (name "Net-(D6-PadA)") (class "Default")
      (node (ref "D6") (pin "A") (pinfunction "A_A") (pintype "passive"))
      (node (ref "R45") (pin "2") (pinfunction "2_2") (pintype "passive"))
    )
    (net (code "44") (name "Net-(D7-PadA)") (class "Default")
      (node (ref "D7") (pin "A") (pinfunction "A_A") (pintype "passive"))
      (node (ref "R41") (pin "2") (pinfunction "2_2") (pintype "passive"))
    )
    (net (code "45") (name "Net-(J3-CC1)") (class "Default")
      (node (ref "J3") (pin "A5") (pinfunction "CC1_A5") (pintype "bidirectional"))
      (node (ref "R7") (pin "2") (pinfunction "2_2") (pintype "passive"))
    )
    (net (code "46") (name "Net-(J3-CC2)") (class "Default")
      (node (ref "J3") (pin "B5") (pinfunction "CC2_B5") (pintype "bidirectional"))
      (node (ref "R8") (pin "2") (pinfunction "2_2") (pintype "passive"))
    )
    (net (code "47") (name "Net-(Q2-B)") (class "Default")
      (node (ref "Q2") (pin "1") (pinfunction "B_1") (pintype "bidirectional"))
      (node (ref "R4") (pin "2") (pinfunction "2_2") (pintype "passive"))
      (node (ref "R5") (pin "2") (pinfunction "2_2") (pintype "passive"))
    )
    (net (code "48") (name "Net-(Q2-C)") (class "Default")
      (node (ref "Q2") (pin "3") (pinfunction "C_3") (pintype "bidirectional"))
      (node (ref "Q3") (pin "1") (pinfunction "G_1") (pintype "passive"))
      (node (ref "R6") (pin "1") (pinfunction "1_1") (pintype "passive"))
    )
    (net (code "49") (name "Net-(Q12-B)") (class "Default")
      (node (ref "Q12") (pin "1") (pinfunction "B_1") (pintype "bidirectional"))
      (node (ref "R14") (pin "2") (pinfunction "2_2") (pintype "passive"))
      (node (ref "R15") (pin "2") (pinfunction "2_2") (pintype "passive"))
    )
    (net (code "50") (name "Net-(Q12-C)") (class "Default")
      (node (ref "Q12") (pin "3") (pinfunction "C_3") (pintype "bidirectional"))
      (node (ref "Q13") (pin "1") (pinfunction "G_1") (pintype "passive"))
      (node (ref "R16") (pin "1") (pinfunction "1_1") (pintype "passive"))
    )
    (net (code "51") (name "Net-(Q22-B)") (class "Default")
      (node (ref "Q22") (pin "1") (pinfunction "B_1") (pintype "bidirectional"))
      (node (ref "R24") (pin "2") (pinfunction "2_2") (pintype "passive"))
      (node (ref "R25") (pin "2") (pinfunction "2_2") (pintype "passive"))
    )
    (net (code "52") (name "Net-(Q22-C)") (class "Default")
      (node (ref "Q22") (pin "3") (pinfunction "C_3") (pintype "bidirectional"))
      (node (ref "Q23") (pin "1") (pinfunction "G_1") (pintype "passive"))
      (node (ref "R26") (pin "1") (pinfunction "1_1") (pintype "passive"))
    )
    (net (code "53") (name "Net-(Q32-B)") (class "Default")
      (node (ref "Q32") (pin "1") (pinfunction "B_1") (pintype "bidirectional"))
      (node (ref "R34") (pin "2") (pinfunction "2_2") (pintype "passive"))
      (node (ref "R35") (pin "2") (pinfunction "2_2") (pintype "passive"))
    )
    (net (code "54") (name "Net-(Q32-C)") (class "Default")
      (node (ref "Q32") (pin "3") (pinfunction "C_3") (pintype "bidirectional"))
      (node (ref "Q33") (pin "1") (pinfunction "G_1") (pintype "passive"))
      (node (ref "R36") (pin "1") (pinfunction "1_1") (pintype "passive"))
    )
    (net (code "55") (name "Net-(U1-VDDCORE)") (class "Default")
      (node (ref "C5") (pin "1") (pinfunction "1_1") (pintype "passive"))
      (node (ref "U1") (pin "29") (pinfunction "VDDCORE_29") (pintype "bidirectional"))
    )
    (net (code "56") (name "Net-(U3-P0.26{slash}XL2)") (class "Default")
      (node (ref "U3") (pin "9") (pinfunction "P0.26/XL2_9") (pintype "bidirectional"))
      (node (ref "Y1") (pin "1") (pinfunction "1_1") (pintype "passive"))
    )
    (net (code "57") (name "Net-(U3-P0.27{slash}XL1)") (class "Default")
      (node (ref "U3") (pin "10") (pinfunction "P0.27/XL1_10") (pintype "bidirectional"))
      (node (ref "Y1") (pin "4") (pinfunction "2_4") (pintype "passive"))
    )
    (net (code "58") (name "VBUS") (class "Default")
      (node (ref "D4") (pin "1") (pinfunction "A1_1") (pintype "passive"))
      (node (ref "J3") (pin "A4-B9") (pinfunction "VBUS_2_A4-B9") (pintype "power_in"))
      (node (ref "J3") (pin "A9-B4") (pinfunction "VBUS_A9-B4") (pintype "power_in"))
      (node (ref "TVS1") (pin "2") (pinfunction "2_2") (pintype "passive"))
    )
    (net (code "59") (name "unconnected-(J1-Pad6)") (class "Default")
      (node (ref "J1") (pin "6") (pinfunction "6_6") (pintype "passive"))
    )
    (net (code "60") (name "unconnected-(J2-Pad6)") (class "Default")
      (node (ref "J2") (pin "6") (pinfunction "6_6") (pintype "passive"))
    )
    (net (code "61") (name "unconnected-(J3-SBU1-PadA8)") (class "Default")
      (node (ref "J3") (pin "A8") (pinfunction "SBU1_A8") (pintype "bidirectional"))
    )
    (net (code "62") (name "unconnected-(J3-SBU2-PadB8)") (class "Default")
      (node (ref "J3") (pin "B8") (pinfunction "SBU2_B8") (pintype "bidirectional"))
    )
    (net (code "63") (name "unconnected-(J22-Pad6)") (class "Default")
      (node (ref "J22") (pin "6") (pinfunction "6_6") (pintype "passive"))
    )
    (net (code "64") (name "unconnected-(U1-PA00-Pad1)") (class "Default")
      (node (ref "U1") (pin "1") (pinfunction "PA00_1") (pintype "bidirectional"))
    )
    (net (code "65") (name "unconnected-(U1-PA01-Pad2)") (class "Default")
      (node (ref "U1") (pin "2") (pinfunction "PA01_2") (pintype "bidirectional"))
    )
    (net (code "66") (name "unconnected-(U1-PA03-Pad4)") (class "Default")
      (node (ref "U1") (pin "4") (pinfunction "PA03_4") (pintype "bidirectional"))
    )
    (net (code "67") (name "unconnected-(U1-PA04-Pad5)") (class "Default")
      (node (ref "U1") (pin "5") (pinfunction "PA04_5") (pintype "bidirectional"))
    )
    (net (code "68") (name "unconnected-(U1-PA10-Pad13)") (class "Default")
      (node (ref "U1") (pin "13") (pinfunction "PA10_13") (pintype "bidirectional"))
    )
    (net (code "69") (name "unconnected-(U1-PA11-Pad14)") (class "Default")
      (node (ref "U1") (pin "14") (pinfunction "PA11_14") (pintype "bidirectional"))
    )
    (net (code "70") (name "unconnected-(U1-PA27-Pad25)") (class "Default")
      (node (ref "U1") (pin "25") (pinfunction "PA27_25") (pintype "bidirectional"))
    )
    (net (code "71") (name "unconnected-(U1-PA28-Pad27)") (class "Default")
      (node (ref "U1") (pin "27") (pinfunction "PA28_27") (pintype "bidirectional"))
    )
    (net (code "72") (name "unconnected-(U3-DCC-Pad15)") (class "Default")
      (node (ref "U3") (pin "15") (pinfunction "DCC_15") (pintype "bidirectional"))
    )
    (net (code "73") (name "unconnected-(U3-DEC2-Pad41)") (class "Default")
      (node (ref "U3") (pin "41") (pinfunction "DEC2_41") (pintype "bidirectional"))
    )
    (net (code "74") (name "unconnected-(U3-P0.00-Pad17)") (class "Default")
      (node (ref "U3") (pin "17") (pinfunction "P0.00_17") (pintype "bidirectional"))
    )
    (net (code "75") (name "unconnected-(U3-P0.02-Pad19)") (class "Default")
      (node (ref "U3") (pin "19") (pinfunction "P0.02_19") (pintype "bidirectional"))
    )
    (net (code "76") (name "unconnected-(U3-P0.03-Pad20)") (class "Default")
      (node (ref "U3") (pin "20") (pinfunction "P0.03_20") (pintype "bidirectional"))
    )
    (net (code "77") (name "unconnected-(U3-P0.04-Pad21)") (class "Default")
      (node (ref "U3") (pin "21") (pinfunction "P0.04_21") (pintype "bidirectional"))
    )
    (net (code "78") (name "unconnected-(U3-P0.05-Pad22)") (class "Default")
      (node (ref "U3") (pin "22") (pinfunction "P0.05_22") (pintype "bidirectional"))
    )
    (net (code "79") (name "unconnected-(U3-P0.06-Pad23)") (class "Default")
      (node (ref "U3") (pin "23") (pinfunction "P0.06_23") (pintype "bidirectional"))
    )
    (net (code "80") (name "unconnected-(U3-P0.07-Pad24)") (class "Default")
      (node (ref "U3") (pin "24") (pinfunction "P0.07_24") (pintype "bidirectional"))
    )
    (net (code "81") (name "unconnected-(U3-P0.12-Pad30)") (class "Default")
      (node (ref "U3") (pin "30") (pinfunction "P0.12_30") (pintype "bidirectional"))
    )
    (net (code "82") (name "unconnected-(U3-P0.13-Pad31)") (class "Default")
      (node (ref "U3") (pin "31") (pinfunction "P0.13_31") (pintype "bidirectional"))
    )
    (net (code "83") (name "unconnected-(U3-P0.14-Pad32)") (class "Default")
      (node (ref "U3") (pin "32") (pinfunction "P0.14_32") (pintype "bidirectional"))
    )
    (net (code "84") (name "unconnected-(U3-P0.15-Pad33)") (class "Default")
      (node (ref "U3") (pin "33") (pinfunction "P0.15_33") (pintype "bidirectional"))
    )
    (net (code "85") (name "unconnected-(U3-P0.17-Pad37)") (class "Default")
      (node (ref "U3") (pin "37") (pinfunction "P0.17_37") (pintype "bidirectional"))
    )
    (net (code "86") (name "unconnected-(U3-P0.20-Pad40)") (class "Default")
      (node (ref "U3") (pin "40") (pinfunction "P0.20_40") (pintype "bidirectional"))
    )
    (net (code "87") (name "unconnected-(U3-P0.21-Pad4)") (class "Default")
      (node (ref "U3") (pin "4") (pinfunction "P0.21_4") (pintype "bidirectional"))
    )
    (net (code "88") (name "unconnected-(U3-P0.22-Pad5)") (class "Default")
      (node (ref "U3") (pin "5") (pinfunction "P0.22_5") (pintype "bidirectional"))
    )
    (net (code "89") (name "unconnected-(U3-P0.23-Pad6)") (class "Default")
      (node (ref "U3") (pin "6") (pinfunction "P0.23_6") (pintype "bidirectional"))
    )
    (net (code "90") (name "unconnected-(U3-P0.24-Pad7)") (class "Default")
      (node (ref "U3") (pin "7") (pinfunction "P0.24_7") (pintype "bidirectional"))
    )
    (net (code "91") (name "unconnected-(U3-P0.25-Pad8)") (class "Default")
      (node (ref "U3") (pin "8") (pinfunction "P0.25_8") (pintype "bidirectional"))
    )
    (net (code "92") (name "unconnected-(U3-P0.28-Pad11)") (class "Default")
      (node (ref "U3") (pin "11") (pinfunction "P0.28_11") (pintype "bidirectional"))
    )
    (net (code "93") (name "unconnected-(U3-P0.29-Pad12)") (class "Default")
      (node (ref "U3") (pin "12") (pinfunction "P0.29_12") (pintype "bidirectional"))
    )
  )
)
